# CATS-FAT-Battery-Interface.net
KiCad netlist of a schematic drawn in Altium Designer
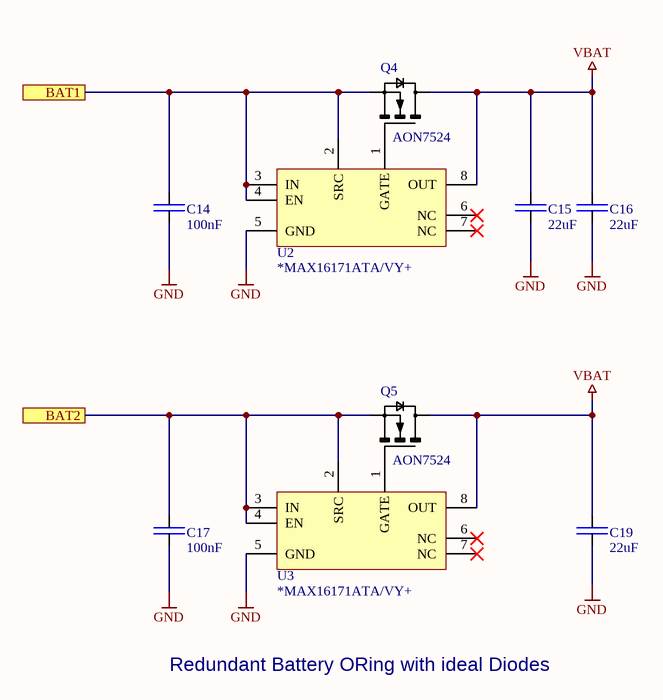
[diagram p0: CATS-FAT-Battery-Interface.SchDoc]

(export (version "E")
  (design (tool "Eeschema 10.0.6"))
  (components
    (comp (ref "C14")
      (value "100nF")
      (footprint "SMD Keramikkondensator 0603")
      (description "SMD Ceramic Capacitor E6")
      (libsource (lib "Ceramic Capacitors-E6") (part "E6 - 100nF"))
    )
    (comp (ref "C15")
      (value "22uF")
      (footprint "SMD Keramikkondensator 0805")
      (description "SMD Ceramic Capacitor E6")
      (libsource (lib "Ceramic Capacitors-E6") (part "E6 - 22uF"))
    )
    (comp (ref "C16")
      (value "22uF")
      (footprint "SMD Keramikkondensator 0805")
      (description "SMD Ceramic Capacitor E6")
      (libsource (lib "Ceramic Capacitors-E6") (part "E6 - 22uF"))
    )
    (comp (ref "C17")
      (value "100nF")
      (footprint "SMD Keramikkondensator 0603")
      (description "SMD Ceramic Capacitor E6")
      (libsource (lib "Ceramic Capacitors-E6") (part "E6 - 100nF"))
    )
    (comp (ref "C19")
      (value "22uF")
      (footprint "SMD Keramikkondensator 0805")
      (description "SMD Ceramic Capacitor E6")
      (libsource (lib "Ceramic Capacitors-E6") (part "E6 - 22uF"))
    )
    (comp (ref "Q4")
      (value "AON7524")
      (footprint "SMD MOSFET DFN 3x3 EP")
      (description "N-Channel 30V 25A (Ta), 28A (Tc) 3.1W (Ta), 32W (Tc) Surface Mount 8-DFN (3x3)")
      (libsource (lib "Electronic Switches") (part "AON7524"))
    )
    (comp (ref "Q5")
      (value "AON7524")
      (footprint "SMD MOSFET DFN 3x3 EP")
      (description "N-Channel 30V 25A (Ta), 28A (Tc) 3.1W (Ta), 32W (Tc) Surface Mount 8-DFN (3x3)")
      (libsource (lib "Electronic Switches") (part "AON7524"))
    )
    (comp (ref "U2")
      (value "*MAX16171ATA/VY+")
      (footprint "SMD IC TDFN-8")
      (description "OR Controller N+1 ORing Controller N-Channel 1:1 8-TDFN-CU (2x3)")
      (libsource (lib "Power Management") (part "MAX16171ATA/VY+"))
    )
    (comp (ref "U3")
      (value "*MAX16171ATA/VY+")
      (footprint "SMD IC TDFN-8")
      (description "OR Controller N+1 ORing Controller N-Channel 1:1 8-TDFN-CU (2x3)")
      (libsource (lib "Power Management") (part "MAX16171ATA/VY+"))
    )
  )
  (nets
    (net (code "1") (name "/BAT1") (class "Default")
      (node (ref "C14") (pin "2") (pinfunction "2_2") (pintype "passive"))
      (node (ref "Q4") (pin "S") (pinfunction "S_S") (pintype "passive"))
      (node (ref "U2") (pin "2") (pinfunction "SRC_2") (pintype "passive"))
      (node (ref "U2") (pin "3") (pinfunction "IN_3") (pintype "passive"))
      (node (ref "U2") (pin "4") (pinfunction "EN_4") (pintype "passive"))
    )
    (net (code "2") (name "/BAT2") (class "Default")
      (node (ref "C17") (pin "2") (pinfunction "2_2") (pintype "passive"))
      (node (ref "Q5") (pin "S") (pinfunction "S_S") (pintype "passive"))
      (node (ref "U3") (pin "2") (pinfunction "SRC_2") (pintype "passive"))
      (node (ref "U3") (pin "3") (pinfunction "IN_3") (pintype "passive"))
      (node (ref "U3") (pin "4") (pinfunction "EN_4") (pintype "passive"))
    )
    (net (code "3") (name "GND") (class "Default")
      (node (ref "C14") (pin "1") (pinfunction "1_1") (pintype "passive"))
      (node (ref "C15") (pin "1") (pinfunction "1_1") (pintype "passive"))
      (node (ref "C16") (pin "1") (pinfunction "1_1") (pintype "passive"))
      (node (ref "C17") (pin "1") (pinfunction "1_1") (pintype "passive"))
      (node (ref "C19") (pin "1") (pinfunction "1_1") (pintype "passive"))
      (node (ref "U2") (pin "5") (pinfunction "GND_5") (pintype "passive"))
      (node (ref "U3") (pin "5") (pinfunction "GND_5") (pintype "passive"))
    )
    (net (code "4") (name "Net-(U2-GATE)") (class "Default")
      (node (ref "Q4") (pin "G") (pinfunction "G_G") (pintype "passive"))
      (node (ref "U2") (pin "1") (pinfunction "GATE_1") (pintype "passive"))
    )
    (net (code "5") (name "Net-(U3-GATE)") (class "Default")
      (node (ref "Q5") (pin "G") (pinfunction "G_G") (pintype "passive"))
      (node (ref "U3") (pin "1") (pinfunction "GATE_1") (pintype "passive"))
    )
    (net (code "6") (name "VBAT") (class "Default")
      (node (ref "C15") (pin "2") (pinfunction "2_2") (pintype "passive"))
      (node (ref "C16") (pin "2") (pinfunction "2_2") (pintype "passive"))
      (node (ref "C19") (pin "2") (pinfunction "2_2") (pintype "passive"))
      (node (ref "Q4") (pin "D") (pinfunction "D_D") (pintype "passive"))
      (node (ref "Q5") (pin "D") (pinfunction "D_D") (pintype "passive"))
      (node (ref "U2") (pin "8") (pinfunction "OUT_8") (pintype "passive"))
      (node (ref "U3") (pin "8") (pinfunction "OUT_8") (pintype "passive"))
    )
    (net (code "7") (name "unconnected-(U2-NC-Pad6)") (class "Default")
      (node (ref "U2") (pin "6") (pinfunction "NC_6") (pintype "passive+no_connect"))
    )
    (net (code "8") (name "unconnected-(U2-NC-Pad7)") (class "Default")
      (node (ref "U2") (pin "7") (pinfunction "NC_7") (pintype "passive+no_connect"))
    )
    (net (code "9") (name "unconnected-(U3-NC-Pad6)") (class "Default")
      (node (ref "U3") (pin "6") (pinfunction "NC_6") (pintype "passive+no_connect"))
    )
    (net (code "10") (name "unconnected-(U3-NC-Pad7)") (class "Default")
      (node (ref "U3") (pin "7") (pinfunction "NC_7") (pintype "passive+no_connect"))
    )
  )
)
